# sch.net
KiCad netlist of a schematic drawn in Altium Designer
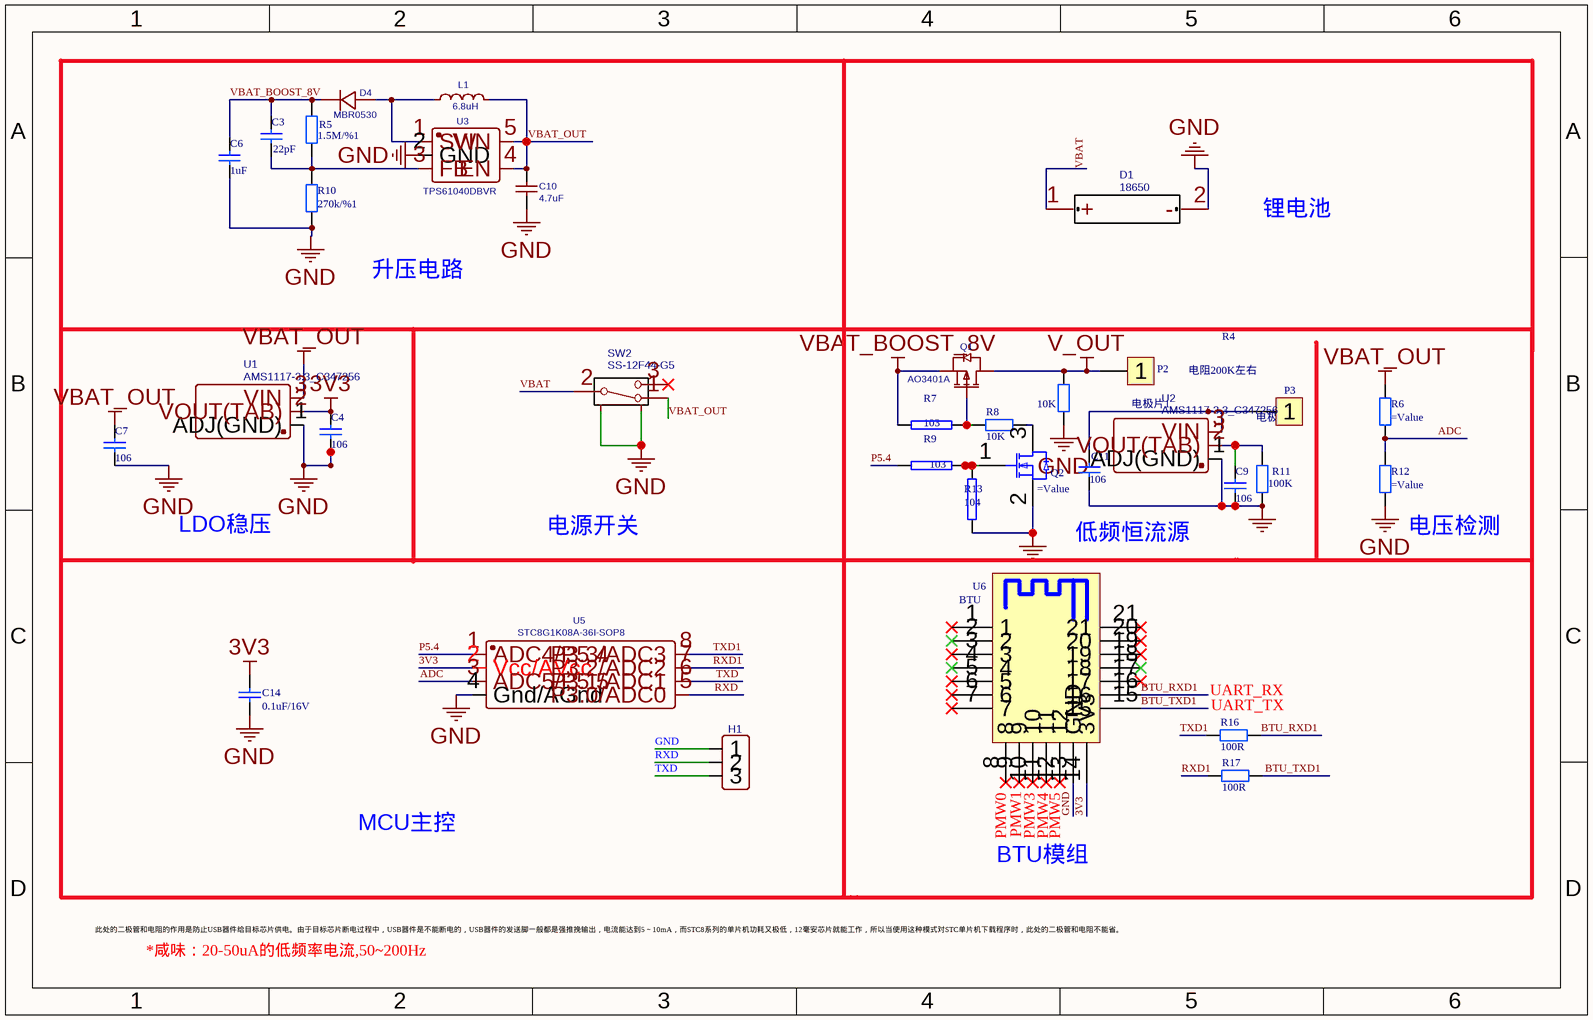
[diagram p0: sch.schdoc]

(export (version "E")
  (design (tool "Eeschema 10.0.6"))
  (components
    (comp (ref "C3")
      (value "22pF")
      (fields (field (name "PART NUMBER") "1.02.05.00869"))
      (libsource (lib "altium-import") (part "root_3_22pF_"))
    )
    (comp (ref "C4")
      (value "106")
      (fields (field (name "PART NUMBER") "1.02.05.00869"))
      (libsource (lib "altium-import") (part "root_3_106_"))
    )
    (comp (ref "C6")
      (value "1uF")
      (fields (field (name "PART NUMBER") "1.02.05.00869"))
      (libsource (lib "altium-import") (part "root_3_1uF_"))
    )
    (comp (ref "C7")
      (value "106")
      (fields (field (name "PART NUMBER") "1.02.05.00869"))
      (libsource (lib "altium-import") (part "root_3_106_"))
    )
    (comp (ref "C9")
      (value "106")
      (fields (field (name "PART NUMBER") "1.02.05.00869"))
      (libsource (lib "altium-import") (part "root_3_106_"))
    )
    (comp (ref "C10")
      (value "4.7uF")
      (fields
        (field (name "BOM_MANUFACTURER PART") "JMK212BJ475KG-T")
        (field (name "BOM_SUPPLIER PART") "C92788")
      )
      (libsource (lib "altium-import") (part "root_1_4.7uF_"))
    )
    (comp (ref "C11")
      (value "106")
      (fields (field (name "PART NUMBER") "1.02.05.00869"))
      (libsource (lib "altium-import") (part "root_3_106_"))
    )
    (comp (ref "C14")
      (value "0.1uF/50V")
      (fields (field (name "PART NUMBER") "1.02.05.00834") (field (name "修改人") "system"))
      (libsource (lib "altium-import") (part "root_1_0.1uF/50V_"))
    )
    (comp (ref "D1")
      (value "18650")
      (fields (field (name "BOM_MANUFACTURER PART") "PIN4") (field (name "CONTRIBUTOR") "tell668"))
      (libsource (lib "altium-import") (part "root_0_18650_"))
    )
    (comp (ref "D4")
      (value "MBR0530")
      (fields (field (name "BOM_SUPPLIER PART") "C475718") (field (name "CONTRIBUTOR") "LCSC"))
      (libsource (lib "altium-import") (part "root_0_MBR0530_"))
    )
    (comp (ref "H1")
      (value "HDR-F-2.54_1x3")
      (fields (field (name "BOM_SUPPLIER PART") "C146690") (field (name "CONTRIBUTOR") "LCEDA_Lib"))
      (libsource (lib "altium-import") (part "root_0_HDR-F-2.54_1x3_"))
    )
    (comp (ref "L1")
      (value "6.8uH")
      (fields
        (field (name "BOM_SUPPLIER PART") "C323532")
        (field (name "BOM_MANUFACTURER PART") "CDRH3D23NP-6R8PC")
        (field (name "CONTRIBUTOR") "LCSC")
      )
      (libsource (lib "altium-import") (part "root_0_6.8uH_"))
    )
    (comp (ref "P2") (value "CON1") (libsource (lib "altium-import") (part "root_0_CON1_")))
    (comp (ref "P3") (value "CON1") (libsource (lib "altium-import") (part "root_0_CON1_")))
    (comp (ref "Q1")
      (value "AO3401A")
      (fields (field (name "BOM_SUPPLIER PART") "C700954") (field (name "CONTRIBUTOR") "LCSC"))
      (libsource (lib "altium-import") (part "root_1_AO3401A_"))
    )
    (comp (ref "Q2")
      (value "CJ2312")
      (fields
        (field (name "PART NUMBER") "1.06.11.00008")
        (field (name "ORCAD LIBRARY PATH") "‪Z:\\tuya_lib\\sch-lib\\DISCRETE.OLB")
        (field (name "修改人") "system")
      )
      (libsource (lib "altium-import") (part "root_0_CJ2312_"))
    )
    (comp (ref "R4") (value "100K/1%") (libsource (lib "altium-import") (part "root_3_100K/1%_")))
    (comp (ref "R5") (value "100K/1%") (libsource (lib "altium-import") (part "root_1_100K/1%_")))
    (comp (ref "R6") (value "100K/1%") (libsource (lib "altium-import") (part "root_1_100K/1%_")))
    (comp (ref "R7") (value "103") (libsource (lib "altium-import") (part "root_0_103_")))
    (comp (ref "R8") (value "100K/1%") (libsource (lib "altium-import") (part "root_0_100K/1%_")))
    (comp (ref "R9") (value "103") (libsource (lib "altium-import") (part "root_0_103_")))
    (comp (ref "R10") (value "100K/1%") (libsource (lib "altium-import") (part "root_1_100K/1%_")))
    (comp (ref "R11") (value "100K/1%") (libsource (lib "altium-import") (part "root_1_100K/1%_")))
    (comp (ref "R12") (value "100K/1%") (libsource (lib "altium-import") (part "root_1_100K/1%_")))
    (comp (ref "R13") (value "104") (libsource (lib "altium-import") (part "root_1_104_")))
    (comp (ref "R16")
      (value "100R")
      (fields (field (name "PART NUMBER") "1.01.01.00808"))
      (libsource (lib "altium-import") (part "root_2_100R_"))
    )
    (comp (ref "R17")
      (value "100R")
      (fields (field (name "PART NUMBER") "1.01.01.00808"))
      (libsource (lib "altium-import") (part "root_2_100R_"))
    )
    (comp (ref "SW2")
      (value "SS-12F44-G5")
      (fields (field (name "BOM_SUPPLIER PART") "C136718") (field (name "CONTRIBUTOR") "LCSC"))
      (libsource (lib "altium-import") (part "root_0_SS-12F44-G5_"))
    )
    (comp (ref "U1")
      (value "AMS1117-3.3_C347256")
      (fields
        (field (name "BOM_SUPPLIER PART") "C347256")
        (field (name "BOM_MANUFACTURER PART") "AMS1117-3.3")
        (field (name "CONTRIBUTOR") "LCSC")
      )
      (libsource (lib "altium-import") (part "root_2_AMS1117-3.3_C347256_"))
    )
    (comp (ref "U2")
      (value "AMS1117-3.3_C347256")
      (fields
        (field (name "BOM_SUPPLIER PART") "C347256")
        (field (name "BOM_MANUFACTURER PART") "AMS1117-3.3")
        (field (name "CONTRIBUTOR") "LCSC")
      )
      (libsource (lib "altium-import") (part "root_2_AMS1117-3.3_C347256_"))
    )
    (comp (ref "U3")
      (value "TPS61040DBVR")
      (fields (field (name "BOM_SUPPLIER PART") "C7722"))
      (libsource (lib "altium-import") (part "root_0_TPS61040DBVR_"))
    )
    (comp (ref "U5")
      (value "STC8G1K08A-36I-SOP8")
      (fields (field (name "BOM_SUPPLIER PART") "C915663") (field (name "CONTRIBUTOR") "LCSC"))
      (libsource (lib "altium-import") (part "root_0_STC8G1K08A-36I-SOP8_"))
    )
    (comp (ref "U6")
      (value "CBU")
      (fields (field (name "PART NUMBER") "0110"))
      (libsource (lib "altium-import") (part "root_0_CBU_"))
    )
  )
  (nets
    (net (code "1") (name "/ADC") (class "Default")
      (node (ref "R12") (pin "2") (pinfunction "2_2") (pintype "passive"))
      (node (ref "R6") (pin "1") (pinfunction "1_1") (pintype "passive"))
      (node (ref "U5") (pin "3") (pinfunction "ADC5/P5.5_3") (pintype "passive"))
    )
    (net (code "2") (name "/BTU_RXD1") (class "Default")
      (node (ref "R16") (pin "1") (pinfunction "1_1") (pintype "passive"))
      (node (ref "U6") (pin "16") (pinfunction "16_16") (pintype "passive"))
    )
    (net (code "3") (name "/BTU_TXD1") (class "Default")
      (node (ref "R17") (pin "1") (pinfunction "1_1") (pintype "passive"))
      (node (ref "U6") (pin "15") (pinfunction "15_15") (pintype "passive"))
    )
    (net (code "4") (name "/P5.4") (class "Default")
      (node (ref "R9") (pin "1") (pintype "passive"))
      (node (ref "U5") (pin "1") (pinfunction "ADC4/P5.4_1") (pintype "passive"))
    )
    (net (code "5") (name "/RXD") (class "Default")
      (node (ref "H1") (pin "2") (pinfunction "2_2") (pintype "passive"))
      (node (ref "U5") (pin "5") (pinfunction "P3.0/ADC0_5") (pintype "passive"))
    )
    (net (code "6") (name "/RXD1") (class "Default")
      (node (ref "R17") (pin "2") (pinfunction "2_2") (pintype "passive"))
      (node (ref "U5") (pin "7") (pinfunction "P3.2/ADC2_7") (pintype "passive"))
    )
    (net (code "7") (name "/TXD") (class "Default")
      (node (ref "H1") (pin "3") (pinfunction "3_3") (pintype "passive"))
      (node (ref "U5") (pin "6") (pinfunction "P3.1/ADC1_6") (pintype "passive"))
    )
    (net (code "8") (name "/TXD1") (class "Default")
      (node (ref "R16") (pin "2") (pinfunction "2_2") (pintype "passive"))
      (node (ref "U5") (pin "8") (pinfunction "P3.3/ADC3_8") (pintype "passive"))
    )
    (net (code "9") (name "/VBAT") (class "Default")
      (node (ref "D1") (pin "1") (pinfunction "+_1") (pintype "passive"))
      (node (ref "SW2") (pin "2") (pinfunction "2_2") (pintype "passive"))
    )
    (net (code "10") (name "3V3") (class "Default")
      (node (ref "C14") (pin "2") (pinfunction "2_2") (pintype "passive"))
      (node (ref "C4") (pin "1") (pinfunction "1_1") (pintype "passive"))
      (node (ref "U1") (pin "2") (pinfunction "VOUT(TAB)_2") (pintype "passive"))
      (node (ref "U5") (pin "2") (pinfunction "Vcc/AVcc_2") (pintype "passive"))
      (node (ref "U6") (pin "14") (pinfunction "3V3_14") (pintype "passive"))
    )
    (net (code "11") (name "GND") (class "Default")
      (node (ref "C10") (pin "1") (pinfunction "1_1") (pintype "passive"))
      (node (ref "C11") (pin "2") (pinfunction "2_2") (pintype "passive"))
      (node (ref "C14") (pin "1") (pinfunction "1_1") (pintype "passive"))
      (node (ref "C4") (pin "2") (pinfunction "2_2") (pintype "passive"))
      (node (ref "C6") (pin "2") (pinfunction "2_2") (pintype "passive"))
      (node (ref "C7") (pin "2") (pinfunction "2_2") (pintype "passive"))
      (node (ref "C9") (pin "2") (pinfunction "2_2") (pintype "passive"))
      (node (ref "D1") (pin "2") (pinfunction "-_2") (pintype "passive"))
      (node (ref "H1") (pin "1") (pinfunction "1_1") (pintype "passive"))
      (node (ref "Q2") (pin "2") (pinfunction "S_2") (pintype "passive"))
      (node (ref "R10") (pin "1") (pinfunction "1_1") (pintype "passive"))
      (node (ref "R11") (pin "1") (pinfunction "1_1") (pintype "passive"))
      (node (ref "R12") (pin "1") (pinfunction "1_1") (pintype "passive"))
      (node (ref "R13") (pin "1") (pintype "passive"))
      (node (ref "R4") (pin "2") (pinfunction "2_2") (pintype "passive"))
      (node (ref "SW2") (pin "4") (pinfunction "4_4") (pintype "passive"))
      (node (ref "SW2") (pin "5") (pinfunction "5_5") (pintype "passive"))
      (node (ref "U1") (pin "1") (pinfunction "ADJ(GND)_1") (pintype "passive"))
      (node (ref "U2") (pin "1") (pinfunction "ADJ(GND)_1") (pintype "passive"))
      (node (ref "U3") (pin "2") (pinfunction "GND_2") (pintype "passive"))
      (node (ref "U5") (pin "4") (pinfunction "Gnd/AGnd_4") (pintype "passive"))
      (node (ref "U6") (pin "13") (pinfunction "GND_13") (pintype "passive"))
    )
    (net (code "12") (name "Net-(D4-A)") (class "Default")
      (node (ref "D4") (pin "2") (pinfunction "A_2") (pintype "passive"))
      (node (ref "L1") (pin "1") (pinfunction "1_1") (pintype "passive"))
      (node (ref "U3") (pin "1") (pinfunction "SW_1") (pintype "passive"))
    )
    (net (code "13") (name "Net-(Q1-G)") (class "Default")
      (node (ref "Q1") (pin "1") (pinfunction "G_1") (pintype "passive"))
      (node (ref "R7") (pin "2") (pintype "passive"))
      (node (ref "R8") (pin "1") (pinfunction "1_1") (pintype "passive"))
    )
    (net (code "14") (name "Net-(Q2-D)") (class "Default")
      (node (ref "Q2") (pin "3") (pinfunction "D_3") (pintype "passive"))
      (node (ref "R8") (pin "2") (pinfunction "2_2") (pintype "passive"))
    )
    (net (code "15") (name "Net-(Q2-G)") (class "Default")
      (node (ref "Q2") (pin "1") (pinfunction "G_1") (pintype "passive"))
      (node (ref "R13") (pin "2") (pintype "passive"))
      (node (ref "R9") (pin "2") (pintype "passive"))
    )
    (net (code "16") (name "Net-(U2-VIN)") (class "Default")
      (node (ref "C11") (pin "1") (pinfunction "1_1") (pintype "passive"))
      (node (ref "P3") (pin "1") (pinfunction "1_1") (pintype "passive"))
      (node (ref "U2") (pin "3") (pinfunction "VIN_3") (pintype "passive"))
    )
    (net (code "17") (name "Net-(U2-VOUT(TAB))") (class "Default")
      (node (ref "C9") (pin "1") (pinfunction "1_1") (pintype "passive"))
      (node (ref "R11") (pin "2") (pinfunction "2_2") (pintype "passive"))
      (node (ref "U2") (pin "2") (pinfunction "VOUT(TAB)_2") (pintype "passive"))
    )
    (net (code "18") (name "Net-(U3-FB)") (class "Default")
      (node (ref "C3") (pin "2") (pinfunction "2_2") (pintype "passive"))
      (node (ref "R10") (pin "2") (pinfunction "2_2") (pintype "passive"))
      (node (ref "R5") (pin "1") (pinfunction "1_1") (pintype "passive"))
      (node (ref "U3") (pin "3") (pinfunction "FB_3") (pintype "passive"))
    )
    (net (code "19") (name "VBAT_BOOST_8V") (class "Default")
      (node (ref "C3") (pin "1") (pinfunction "1_1") (pintype "passive"))
      (node (ref "C6") (pin "1") (pinfunction "1_1") (pintype "passive"))
      (node (ref "D4") (pin "1") (pinfunction "K_1") (pintype "passive"))
      (node (ref "Q1") (pin "2") (pinfunction "S_2") (pintype "passive"))
      (node (ref "R5") (pin "2") (pinfunction "2_2") (pintype "passive"))
      (node (ref "R7") (pin "1") (pintype "passive"))
    )
    (net (code "20") (name "VBAT_OUT") (class "Default")
      (node (ref "C10") (pin "2") (pinfunction "2_2") (pintype "passive"))
      (node (ref "C7") (pin "1") (pinfunction "1_1") (pintype "passive"))
      (node (ref "L1") (pin "2") (pinfunction "2_2") (pintype "passive"))
      (node (ref "R6") (pin "2") (pinfunction "2_2") (pintype "passive"))
      (node (ref "SW2") (pin "1") (pinfunction "1_1") (pintype "passive"))
      (node (ref "U1") (pin "3") (pinfunction "VIN_3") (pintype "passive"))
      (node (ref "U3") (pin "4") (pinfunction "EN_4") (pintype "passive"))
      (node (ref "U3") (pin "5") (pinfunction "VIN_5") (pintype "passive"))
    )
    (net (code "21") (name "V_OUT") (class "Default")
      (node (ref "P2") (pin "1") (pinfunction "1_1") (pintype "passive"))
      (node (ref "Q1") (pin "3") (pinfunction "D_3") (pintype "passive"))
      (node (ref "R4") (pin "1") (pinfunction "1_1") (pintype "passive"))
    )
    (net (code "22") (name "unconnected-(SW2-Pad3)") (class "Default")
      (node (ref "SW2") (pin "3") (pinfunction "3_3") (pintype "passive+no_connect"))
    )
    (net (code "23") (name "unconnected-(U6-Pad1)") (class "Default")
      (node (ref "U6") (pin "1") (pinfunction "1_1") (pintype "passive+no_connect"))
    )
    (net (code "24") (name "unconnected-(U6-Pad2)") (class "Default")
      (node (ref "U6") (pin "2") (pinfunction "2_2") (pintype "passive+no_connect"))
    )
    (net (code "25") (name "unconnected-(U6-Pad3)") (class "Default")
      (node (ref "U6") (pin "3") (pinfunction "3_3") (pintype "passive+no_connect"))
    )
    (net (code "26") (name "unconnected-(U6-Pad4)") (class "Default")
      (node (ref "U6") (pin "4") (pinfunction "4_4") (pintype "passive+no_connect"))
    )
    (net (code "27") (name "unconnected-(U6-Pad5)") (class "Default")
      (node (ref "U6") (pin "5") (pinfunction "5_5") (pintype "passive+no_connect"))
    )
    (net (code "28") (name "unconnected-(U6-Pad6)") (class "Default")
      (node (ref "U6") (pin "6") (pinfunction "6_6") (pintype "passive+no_connect"))
    )
    (net (code "29") (name "unconnected-(U6-Pad7)") (class "Default")
      (node (ref "U6") (pin "7") (pinfunction "7_7") (pintype "passive+no_connect"))
    )
    (net (code "30") (name "unconnected-(U6-Pad8)") (class "Default")
      (node (ref "U6") (pin "8") (pinfunction "8_8") (pintype "passive+no_connect"))
    )
    (net (code "31") (name "unconnected-(U6-Pad9)") (class "Default")
      (node (ref "U6") (pin "9") (pinfunction "9_9") (pintype "passive+no_connect"))
    )
    (net (code "32") (name "unconnected-(U6-Pad10)") (class "Default")
      (node (ref "U6") (pin "10") (pinfunction "10_10") (pintype "passive+no_connect"))
    )
    (net (code "33") (name "unconnected-(U6-Pad11)") (class "Default")
      (node (ref "U6") (pin "11") (pinfunction "11_11") (pintype "passive+no_connect"))
    )
    (net (code "34") (name "unconnected-(U6-Pad12)") (class "Default")
      (node (ref "U6") (pin "12") (pinfunction "12_12") (pintype "passive+no_connect"))
    )
    (net (code "35") (name "unconnected-(U6-Pad17)") (class "Default")
      (node (ref "U6") (pin "17") (pinfunction "17_17") (pintype "passive+no_connect"))
    )
    (net (code "36") (name "unconnected-(U6-Pad18)") (class "Default")
      (node (ref "U6") (pin "18") (pinfunction "18_18") (pintype "passive+no_connect"))
    )
    (net (code "37") (name "unconnected-(U6-Pad19)") (class "Default")
      (node (ref "U6") (pin "19") (pinfunction "19_19") (pintype "passive+no_connect"))
    )
    (net (code "38") (name "unconnected-(U6-Pad20)") (class "Default")
      (node (ref "U6") (pin "20") (pinfunction "20_20") (pintype "passive+no_connect"))
    )
    (net (code "39") (name "unconnected-(U6-Pad21)") (class "Default")
      (node (ref "U6") (pin "21") (pinfunction "21_21") (pintype "passive+no_connect"))
    )
  )
)
